# EVGP_Estop_Daugherboard.net
KiCad netlist of a schematic drawn in EAGLE
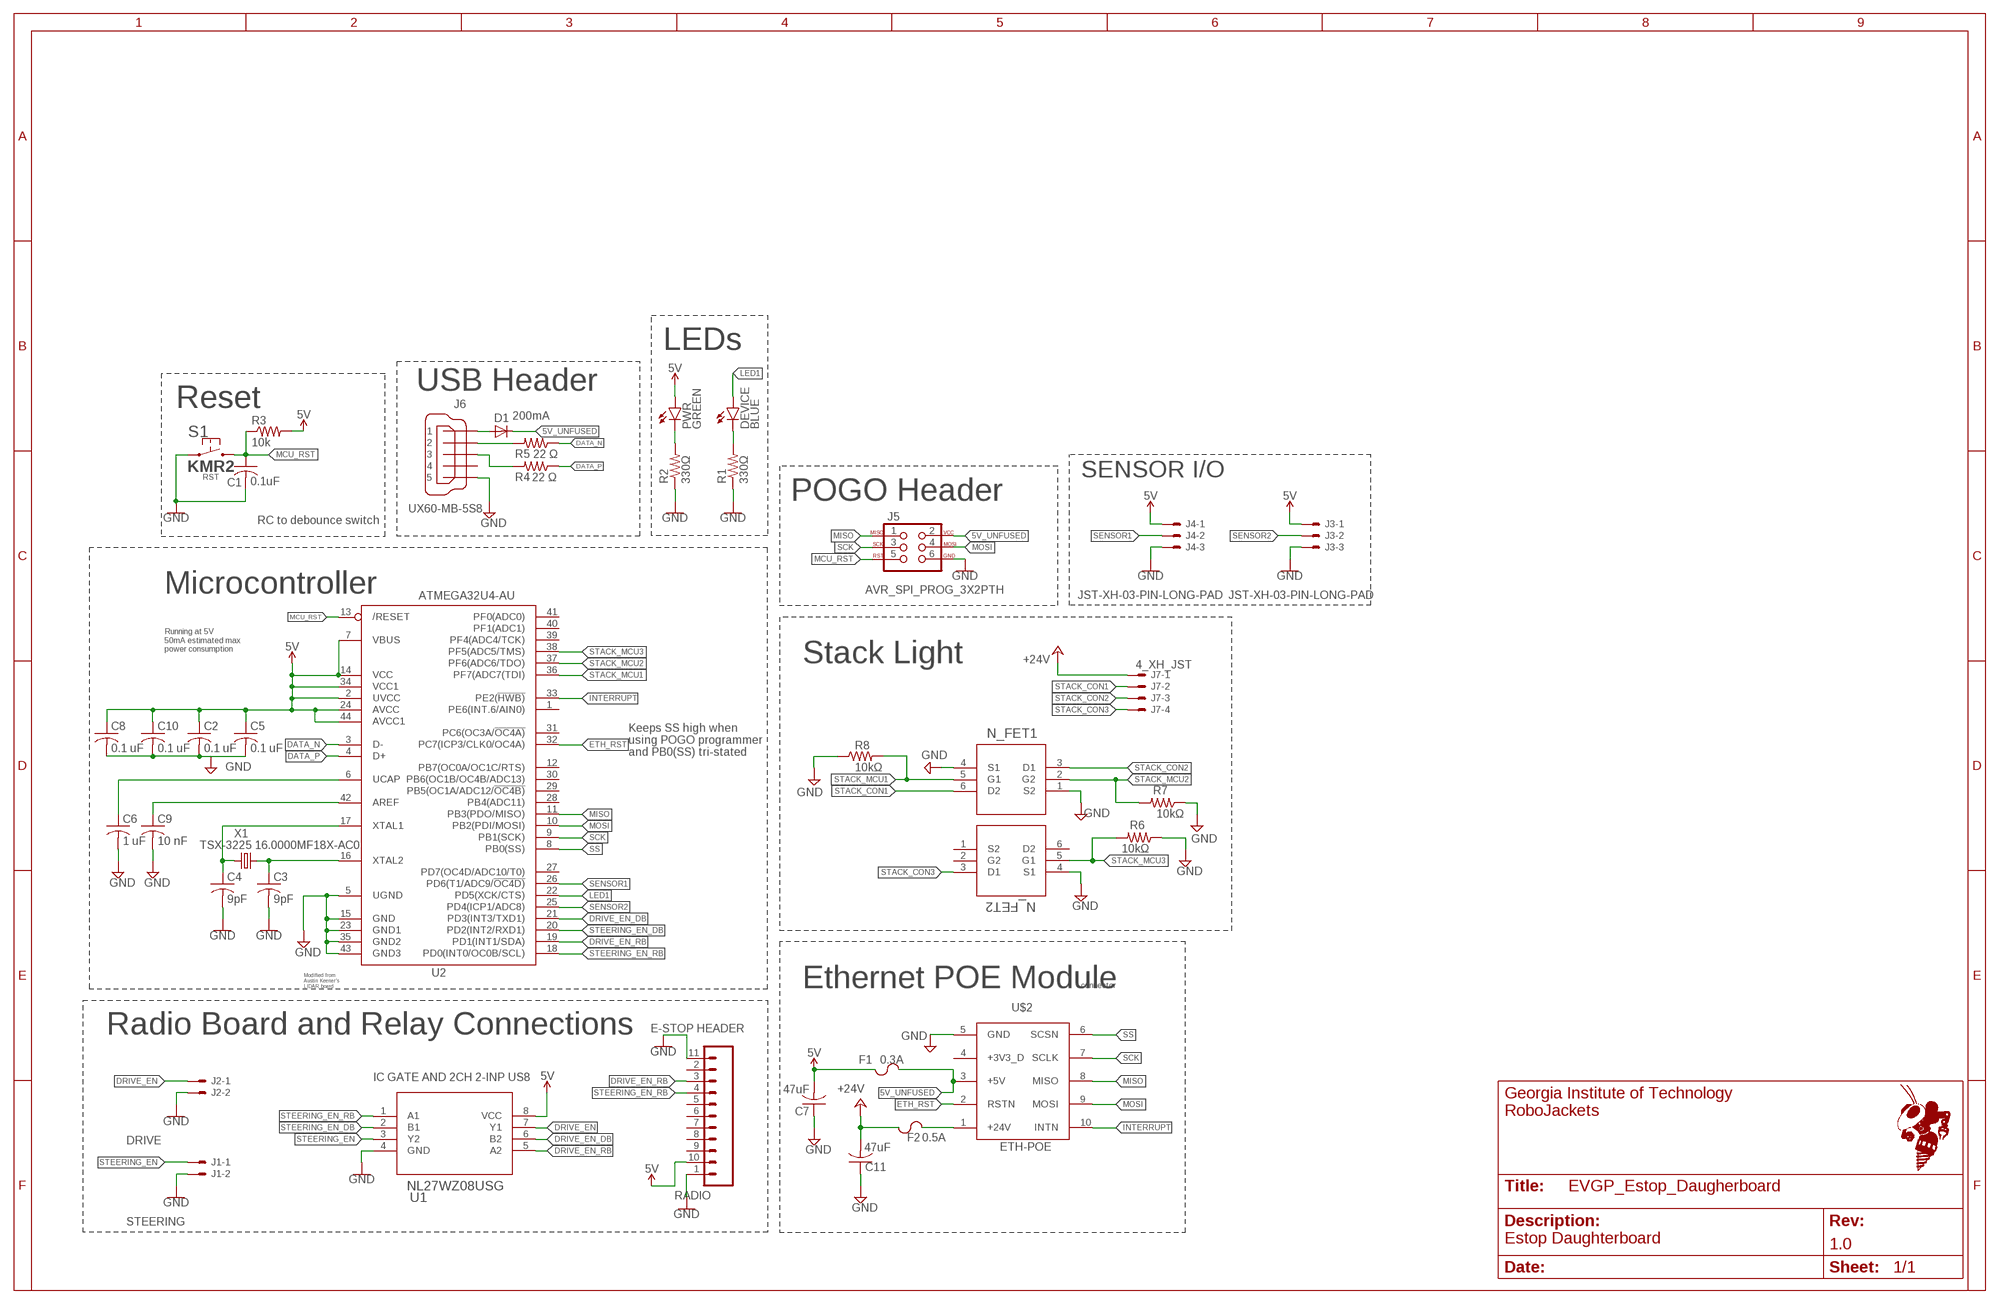
[diagram p0: schematic, sheet 1]

(export (version "E")
  (design (tool "Eeschema 10.0.6"))
  (components
    (comp (ref "C1")
      (value "0.1uF")
      (footprint "eagle-import:C0603")
      (libsource (lib "eagle-import") (part "C-USC0603"))
    )
    (comp (ref "C2")
      (value "0.1 uF")
      (footprint "eagle-import:C0603")
      (libsource (lib "eagle-import") (part "resistor_348_C-USC0603"))
    )
    (comp (ref "C3")
      (value "9pF")
      (footprint "eagle-import:C0603")
      (libsource (lib "eagle-import") (part "resistor_348_C-USC0603"))
    )
    (comp (ref "C4")
      (value "9pF")
      (footprint "eagle-import:C0603")
      (libsource (lib "eagle-import") (part "resistor_348_C-USC0603"))
    )
    (comp (ref "C5")
      (value "0.1 uF")
      (footprint "eagle-import:C0603")
      (libsource (lib "eagle-import") (part "resistor_348_C-USC0603"))
    )
    (comp (ref "C6")
      (value "1 uF")
      (footprint "eagle-import:C0603")
      (libsource (lib "eagle-import") (part "resistor_348_C-USC0603"))
    )
    (comp (ref "C7")
      (value "47uF")
      (footprint "eagle-import:C1206")
      (libsource (lib "eagle-import") (part "C-USC1206"))
    )
    (comp (ref "C8")
      (value "0.1 uF")
      (footprint "eagle-import:C0603")
      (libsource (lib "eagle-import") (part "resistor_348_C-USC0603"))
    )
    (comp (ref "C9")
      (value "10 nF")
      (footprint "eagle-import:C0603")
      (libsource (lib "eagle-import") (part "resistor_348_C-USC0603"))
    )
    (comp (ref "C10")
      (value "0.1 uF")
      (footprint "eagle-import:C0603")
      (libsource (lib "eagle-import") (part "resistor_348_C-USC0603"))
    )
    (comp (ref "C11")
      (value "47uF")
      (footprint "eagle-import:C1206")
      (libsource (lib "eagle-import") (part "C-USC1206"))
    )
    (comp (ref "D1")
      (value "200mA")
      (footprint "eagle-import:SOD323-R")
      (libsource (lib "eagle-import") (part "DIODE-SOD323-R"))
    )
    (comp (ref "DEVICE")
      (value "BLUE")
      (footprint "eagle-import:CHIP-LED0603")
      (libsource (lib "eagle-import") (part "LEDCHIP-LED0603"))
    )
    (comp (ref "F1")
      (value "0.3A")
      (footprint "eagle-import:F1206")
      (libsource (lib "eagle-import") (part "CHIP_FUSE1206"))
    )
    (comp (ref "F2")
      (value "0.5A")
      (footprint "eagle-import:F1206")
      (libsource (lib "eagle-import") (part "CHIP_FUSE1206"))
    )
    (comp (ref "J1")
      (value "STEERING")
      (footprint "eagle-import:JST-XH-02-PACKAGE-LONG-PAD")
      (libsource (lib "eagle-import") (part "JST-XH-02-PIN-LONG-PAD"))
    )
    (comp (ref "J2")
      (value "DRIVE")
      (footprint "eagle-import:JST-XH-02-PACKAGE-LONG-PAD")
      (libsource (lib "eagle-import") (part "JST-XH-02-PIN-LONG-PAD"))
    )
    (comp (ref "J3")
      (value "JST-XH-03-PIN-LONG-PAD")
      (footprint "eagle-import:JST-XH-03-PACKAGE-LONG-PAD")
      (libsource (lib "eagle-import") (part "JST-XH-03-PIN-LONG-PAD"))
    )
    (comp (ref "J4")
      (value "JST-XH-03-PIN-LONG-PAD")
      (footprint "eagle-import:JST-XH-03-PACKAGE-LONG-PAD")
      (libsource (lib "eagle-import") (part "JST-XH-03-PIN-LONG-PAD"))
    )
    (comp (ref "J5")
      (value "AVR_SPI_PROG_3X2PTH")
      (footprint "eagle-import:2X3")
      (libsource (lib "eagle-import") (part "AVR_SPI_PROG_3X2PTH"))
    )
    (comp (ref "J6")
      (value "UX60-MB-5S8")
      (footprint "eagle-import:UX60-MB-5S8")
      (libsource (lib "eagle-import") (part "UX60-MB-5S?8"))
    )
    (comp (ref "J7")
      (value "4_XH_JST")
      (footprint "eagle-import:JST-XH-04-PACKAGE-LONG-PAD")
      (libsource (lib "eagle-import") (part "JST-XH-04-PIN-LONG-PAD"))
    )
    (comp (ref "PWR")
      (value "GREEN")
      (footprint "eagle-import:CHIP-LED0603")
      (libsource (lib "eagle-import") (part "LEDCHIP-LED0603"))
    )
    (comp (ref "Q1")
      (value "N_FET2")
      (footprint "eagle-import:SOT-363")
      (fields (field (name "MANUFACTURER_PART_NUMBER") "BSS84DW7F"))
      (libsource (lib "eagle-import") (part "BSS84DW-7-F"))
    )
    (comp (ref "Q2")
      (value "N_FET1")
      (footprint "eagle-import:SOT-363")
      (fields (field (name "MANUFACTURER_PART_NUMBER") "BSS84DW7F"))
      (libsource (lib "eagle-import") (part "BSS84DW-7-F"))
    )
    (comp (ref "R1")
      (value "330Ω")
      (footprint "eagle-import:R0603")
      (libsource (lib "eagle-import") (part "R-US_R0603"))
    )
    (comp (ref "R2")
      (value "330Ω")
      (footprint "eagle-import:R0603")
      (libsource (lib "eagle-import") (part "R-US_R0603"))
    )
    (comp (ref "R3")
      (value "10k")
      (footprint "eagle-import:R0603")
      (libsource (lib "eagle-import") (part "R-US_R0603"))
    )
    (comp (ref "R4")
      (value "22 Ω")
      (footprint "eagle-import:R0603")
      (libsource (lib "eagle-import") (part "R-US_R0603"))
    )
    (comp (ref "R5")
      (value "22 Ω")
      (footprint "eagle-import:R0603")
      (libsource (lib "eagle-import") (part "R-US_R0603"))
    )
    (comp (ref "R6")
      (value "10kΩ")
      (footprint "eagle-import:R0603")
      (libsource (lib "eagle-import") (part "R-US_R0603"))
    )
    (comp (ref "R7")
      (value "10kΩ")
      (footprint "eagle-import:R0603")
      (libsource (lib "eagle-import") (part "R-US_R0603"))
    )
    (comp (ref "R8")
      (value "10kΩ")
      (footprint "eagle-import:R0603")
      (libsource (lib "eagle-import") (part "R-US_R0603"))
    )
    (comp (ref "RADIO")
      (value "E-STOP HEADER")
      (footprint "eagle-import:RADIO_V1.3")
      (libsource (lib "eagle-import") (part "ESTOP_RADIO"))
    )
    (comp (ref "S1")
      (value "KMR2")
      (footprint "eagle-import:KMR2")
      (fields (field (name "FUNCTION") "Reset") (field (name "FUNCTION_1") "RST"))
      (libsource (lib "eagle-import") (part "KMR2"))
    )
    (comp (ref "U$2")
      (value "ETH-POE")
      (footprint "eagle-import:HDRVR10W64P4000X254_2X5_1016X508X254B")
      (libsource (lib "eagle-import") (part "ETH-POE"))
    )
    (comp (ref "U1")
      (value "NL27WZ08USG")
      (footprint "eagle-import:US8_2P40X2P10")
      (libsource (lib "eagle-import") (part "NL27WZ08USG"))
    )
    (comp (ref "U2")
      (value "ATMEGA32U4-AU")
      (footprint "eagle-import:TQFP44")
      (libsource (lib "eagle-import") (part "ATMEGA32U4-AU"))
    )
    (comp (ref "X1")
      (value "TSX-3225 16.0000MF18X-AC0")
      (footprint "eagle-import:XTAL-3.2X2.5")
      (libsource (lib "eagle-import") (part "XTAL-3.2X2.5"))
    )
  )
  (nets
    (net (code "1") (name "+24V") (class "Default")
      (node (ref "C11") (pin "2") (pinfunction "2_2") (pintype "passive"))
      (node (ref "F2") (pin "1") (pinfunction "1_1") (pintype "bidirectional"))
      (node (ref "J7") (pin "1") (pinfunction "S_1") (pintype "passive"))
    )
    (net (code "2") (name "5V") (class "Default")
      (node (ref "C10") (pin "1") (pinfunction "1_1") (pintype "passive"))
      (node (ref "C2") (pin "1") (pinfunction "1_1") (pintype "passive"))
      (node (ref "C5") (pin "1") (pinfunction "1_1") (pintype "passive"))
      (node (ref "C7") (pin "2") (pinfunction "2_2") (pintype "passive"))
      (node (ref "C8") (pin "1") (pinfunction "1_1") (pintype "passive"))
      (node (ref "F1") (pin "1") (pinfunction "1_1") (pintype "bidirectional"))
      (node (ref "J3") (pin "1") (pinfunction "S_1") (pintype "passive"))
      (node (ref "J4") (pin "1") (pinfunction "S_1") (pintype "passive"))
      (node (ref "PWR") (pin "A") (pinfunction "A_A") (pintype "passive"))
      (node (ref "R3") (pin "2") (pinfunction "2_2") (pintype "passive"))
      (node (ref "RADIO") (pin "10") (pinfunction "5V_10") (pintype "passive"))
      (node (ref "U1") (pin "8") (pinfunction "VCC_8") (pintype "power_in"))
      (node (ref "U2") (pin "14") (pinfunction "VCC_14") (pintype "bidirectional"))
      (node (ref "U2") (pin "2") (pinfunction "UVCC_2") (pintype "bidirectional"))
      (node (ref "U2") (pin "24") (pinfunction "AVCC_24") (pintype "bidirectional"))
      (node (ref "U2") (pin "34") (pinfunction "VCC1_34") (pintype "bidirectional"))
      (node (ref "U2") (pin "44") (pinfunction "AVCC1_44") (pintype "bidirectional"))
      (node (ref "U2") (pin "7") (pinfunction "VBUS_7") (pintype "bidirectional"))
    )
    (net (code "3") (name "5V_UNFUSED") (class "Default")
      (node (ref "D1") (pin "C") (pinfunction "C_C") (pintype "passive"))
      (node (ref "F1") (pin "2") (pinfunction "2_2") (pintype "bidirectional"))
      (node (ref "J5") (pin "2") (pinfunction "2_2") (pintype "passive"))
      (node (ref "U$2") (pin "3") (pinfunction "+5V_3") (pintype "bidirectional"))
    )
    (net (code "4") (name "DATA_N") (class "Default")
      (node (ref "R5") (pin "1") (pinfunction "1_1") (pintype "passive"))
      (node (ref "U2") (pin "3") (pinfunction "D-_3") (pintype "bidirectional"))
    )
    (net (code "5") (name "DATA_P") (class "Default")
      (node (ref "R4") (pin "1") (pinfunction "1_1") (pintype "passive"))
      (node (ref "U2") (pin "4") (pinfunction "D+_4") (pintype "bidirectional"))
    )
    (net (code "6") (name "DRIVE_EN") (class "Default")
      (node (ref "J2") (pin "1") (pinfunction "S_1") (pintype "passive"))
      (node (ref "U1") (pin "7") (pinfunction "Y1_7") (pintype "output"))
    )
    (net (code "7") (name "DRIVE_EN_DB") (class "Default")
      (node (ref "U1") (pin "6") (pinfunction "B2_6") (pintype "input"))
      (node (ref "U2") (pin "21") (pinfunction "PD3(INT3/TXD1)_21") (pintype "bidirectional"))
    )
    (net (code "8") (name "DRIVE_EN_RB") (class "Default")
      (node (ref "RADIO") (pin "3") (pinfunction "D1_3") (pintype "passive"))
      (node (ref "U1") (pin "5") (pinfunction "A2_5") (pintype "input"))
      (node (ref "U2") (pin "19") (pinfunction "PD1(INT1/SDA)_19") (pintype "bidirectional"))
    )
    (net (code "9") (name "ETH_RST") (class "Default")
      (node (ref "U$2") (pin "2") (pinfunction "RSTN_2") (pintype "bidirectional"))
      (node (ref "U2") (pin "32") (pinfunction "PC7(ICP3/CLK0/OC4A)_32") (pintype "bidirectional"))
    )
    (net (code "10") (name "GND") (class "Default")
      (node (ref "C1") (pin "2") (pinfunction "2_2") (pintype "passive"))
      (node (ref "C10") (pin "2") (pinfunction "2_2") (pintype "passive"))
      (node (ref "C11") (pin "1") (pinfunction "1_1") (pintype "passive"))
      (node (ref "C2") (pin "2") (pinfunction "2_2") (pintype "passive"))
      (node (ref "C3") (pin "2") (pinfunction "2_2") (pintype "passive"))
      (node (ref "C4") (pin "2") (pinfunction "2_2") (pintype "passive"))
      (node (ref "C5") (pin "2") (pinfunction "2_2") (pintype "passive"))
      (node (ref "C6") (pin "2") (pinfunction "2_2") (pintype "passive"))
      (node (ref "C7") (pin "1") (pinfunction "1_1") (pintype "passive"))
      (node (ref "C8") (pin "2") (pinfunction "2_2") (pintype "passive"))
      (node (ref "C9") (pin "2") (pinfunction "2_2") (pintype "passive"))
      (node (ref "J1") (pin "2") (pinfunction "S_2") (pintype "passive"))
      (node (ref "J2") (pin "2") (pinfunction "S_2") (pintype "passive"))
      (node (ref "J3") (pin "3") (pinfunction "S_3") (pintype "passive"))
      (node (ref "J4") (pin "3") (pinfunction "S_3") (pintype "passive"))
      (node (ref "J5") (pin "6") (pinfunction "6_6") (pintype "passive"))
      (node (ref "J6") (pin "5") (pinfunction "5_5") (pintype "passive"))
      (node (ref "Q1") (pin "4") (pinfunction "S1_4") (pintype "passive"))
      (node (ref "Q2") (pin "1") (pinfunction "S2_1") (pintype "passive"))
      (node (ref "Q2") (pin "4") (pinfunction "S1_4") (pintype "passive"))
      (node (ref "R1") (pin "1") (pinfunction "1_1") (pintype "passive"))
      (node (ref "R2") (pin "1") (pinfunction "1_1") (pintype "passive"))
      (node (ref "R6") (pin "1") (pinfunction "1_1") (pintype "passive"))
      (node (ref "R7") (pin "1") (pinfunction "1_1") (pintype "passive"))
      (node (ref "R8") (pin "1") (pinfunction "1_1") (pintype "passive"))
      (node (ref "RADIO") (pin "1") (pinfunction "GND_1") (pintype "passive"))
      (node (ref "RADIO") (pin "11") (pinfunction "GND_11") (pintype "passive"))
      (node (ref "S1") (pin "1.1") (pinfunction "1_1.1") (pintype "passive"))
      (node (ref "S1") (pin "1.2") (pinfunction "1_1.2") (pintype "passive"))
      (node (ref "U$2") (pin "5") (pinfunction "GND_5") (pintype "bidirectional"))
      (node (ref "U1") (pin "4") (pinfunction "GND_4") (pintype "power_in"))
      (node (ref "U2") (pin "15") (pinfunction "GND_15") (pintype "bidirectional"))
      (node (ref "U2") (pin "23") (pinfunction "GND1_23") (pintype "bidirectional"))
      (node (ref "U2") (pin "35") (pinfunction "GND2_35") (pintype "bidirectional"))
      (node (ref "U2") (pin "43") (pinfunction "GND3_43") (pintype "bidirectional"))
      (node (ref "U2") (pin "5") (pinfunction "UGND_5") (pintype "bidirectional"))
    )
    (net (code "11") (name "INTERRUPT") (class "Default")
      (node (ref "U$2") (pin "10") (pinfunction "INTN_10") (pintype "bidirectional"))
      (node (ref "U2") (pin "33") (pinfunction "PE2(~{HWB})_33") (pintype "bidirectional"))
    )
    (net (code "12") (name "LED1") (class "Default")
      (node (ref "DEVICE") (pin "A") (pinfunction "A_A") (pintype "passive"))
      (node (ref "U2") (pin "22") (pinfunction "PD5(XCK/CTS)_22") (pintype "bidirectional"))
    )
    (net (code "13") (name "MCU_RST") (class "Default")
      (node (ref "C1") (pin "1") (pinfunction "1_1") (pintype "passive"))
      (node (ref "J5") (pin "5") (pinfunction "5_5") (pintype "passive"))
      (node (ref "R3") (pin "1") (pinfunction "1_1") (pintype "passive"))
      (node (ref "S1") (pin "2.1") (pinfunction "2_2.1") (pintype "passive"))
      (node (ref "S1") (pin "2.2") (pinfunction "2_2.2") (pintype "passive"))
      (node (ref "U2") (pin "13") (pinfunction "/RESET_13") (pintype "bidirectional"))
    )
    (net (code "14") (name "MISO") (class "Default")
      (node (ref "J5") (pin "1") (pinfunction "1_1") (pintype "passive"))
      (node (ref "U$2") (pin "8") (pinfunction "MISO_8") (pintype "bidirectional"))
      (node (ref "U2") (pin "11") (pinfunction "PB3(PDO/MISO)_11") (pintype "bidirectional"))
    )
    (net (code "15") (name "MOSI") (class "Default")
      (node (ref "J5") (pin "4") (pinfunction "4_4") (pintype "passive"))
      (node (ref "U$2") (pin "9") (pinfunction "MOSI_9") (pintype "bidirectional"))
      (node (ref "U2") (pin "10") (pinfunction "PB2(PDI/MOSI)_10") (pintype "bidirectional"))
    )
    (net (code "16") (name "Net-(D1-PadA)") (class "Default")
      (node (ref "D1") (pin "A") (pinfunction "A_A") (pintype "passive"))
      (node (ref "J6") (pin "1") (pinfunction "1_1") (pintype "passive"))
    )
    (net (code "17") (name "Net-(DEVICE-PadC)") (class "Default")
      (node (ref "DEVICE") (pin "C") (pinfunction "C_C") (pintype "passive"))
      (node (ref "R1") (pin "2") (pinfunction "2_2") (pintype "passive"))
    )
    (net (code "18") (name "Net-(J6-Pad2)") (class "Default")
      (node (ref "J6") (pin "2") (pinfunction "2_2") (pintype "passive"))
      (node (ref "R5") (pin "2") (pinfunction "2_2") (pintype "passive"))
    )
    (net (code "19") (name "Net-(J6-Pad3)") (class "Default")
      (node (ref "J6") (pin "3") (pinfunction "3_3") (pintype "passive"))
      (node (ref "R4") (pin "2") (pinfunction "2_2") (pintype "passive"))
    )
    (net (code "20") (name "Net-(PWR-PadC)") (class "Default")
      (node (ref "PWR") (pin "C") (pinfunction "C_C") (pintype "passive"))
      (node (ref "R2") (pin "2") (pinfunction "2_2") (pintype "passive"))
    )
    (net (code "21") (name "Net-(U$2-+24V)") (class "Default")
      (node (ref "F2") (pin "2") (pinfunction "2_2") (pintype "bidirectional"))
      (node (ref "U$2") (pin "1") (pinfunction "+24V_1") (pintype "bidirectional"))
    )
    (net (code "22") (name "Net-(U2-AREF)") (class "Default")
      (node (ref "C9") (pin "1") (pinfunction "1_1") (pintype "passive"))
      (node (ref "U2") (pin "42") (pinfunction "AREF_42") (pintype "bidirectional"))
    )
    (net (code "23") (name "Net-(U2-UCAP)") (class "Default")
      (node (ref "C6") (pin "1") (pinfunction "1_1") (pintype "passive"))
      (node (ref "U2") (pin "6") (pinfunction "UCAP_6") (pintype "bidirectional"))
    )
    (net (code "24") (name "Net-(U2-XTAL1)") (class "Default")
      (node (ref "C4") (pin "1") (pinfunction "1_1") (pintype "passive"))
      (node (ref "U2") (pin "17") (pinfunction "XTAL1_17") (pintype "bidirectional"))
      (node (ref "X1") (pin "1") (pinfunction "1_1") (pintype "passive"))
    )
    (net (code "25") (name "Net-(U2-XTAL2)") (class "Default")
      (node (ref "C3") (pin "1") (pinfunction "1_1") (pintype "passive"))
      (node (ref "U2") (pin "16") (pinfunction "XTAL2_16") (pintype "bidirectional"))
      (node (ref "X1") (pin "3") (pinfunction "2_3") (pintype "passive"))
    )
    (net (code "26") (name "SCK") (class "Default")
      (node (ref "J5") (pin "3") (pinfunction "3_3") (pintype "passive"))
      (node (ref "U$2") (pin "7") (pinfunction "SCLK_7") (pintype "bidirectional"))
      (node (ref "U2") (pin "9") (pinfunction "PB1(SCK)_9") (pintype "bidirectional"))
    )
    (net (code "27") (name "SENSOR1") (class "Default")
      (node (ref "J4") (pin "2") (pinfunction "S_2") (pintype "passive"))
      (node (ref "U2") (pin "26") (pinfunction "PD6(T1/ADC9/~{OC4D})_26") (pintype "bidirectional"))
    )
    (net (code "28") (name "SENSOR2") (class "Default")
      (node (ref "J3") (pin "2") (pinfunction "S_2") (pintype "passive"))
      (node (ref "U2") (pin "25") (pinfunction "PD4(ICP1/ADC8)_25") (pintype "bidirectional"))
    )
    (net (code "29") (name "SS") (class "Default")
      (node (ref "U$2") (pin "6") (pinfunction "SCSN_6") (pintype "bidirectional"))
      (node (ref "U2") (pin "8") (pinfunction "PB0(SS)_8") (pintype "bidirectional"))
    )
    (net (code "30") (name "STACK_CON1") (class "Default")
      (node (ref "J7") (pin "2") (pinfunction "S_2") (pintype "passive"))
      (node (ref "Q2") (pin "6") (pinfunction "D2_6") (pintype "passive"))
    )
    (net (code "31") (name "STACK_CON2") (class "Default")
      (node (ref "J7") (pin "3") (pinfunction "S_3") (pintype "passive"))
      (node (ref "Q2") (pin "3") (pinfunction "D1_3") (pintype "passive"))
    )
    (net (code "32") (name "STACK_CON3") (class "Default")
      (node (ref "J7") (pin "4") (pinfunction "S_4") (pintype "passive"))
      (node (ref "Q1") (pin "3") (pinfunction "D1_3") (pintype "passive"))
    )
    (net (code "33") (name "STACK_MCU1") (class "Default")
      (node (ref "Q2") (pin "5") (pinfunction "G1_5") (pintype "passive"))
      (node (ref "R8") (pin "2") (pinfunction "2_2") (pintype "passive"))
      (node (ref "U2") (pin "36") (pinfunction "PF7(ADC7(TDI)_36") (pintype "bidirectional"))
    )
    (net (code "34") (name "STACK_MCU2") (class "Default")
      (node (ref "Q2") (pin "2") (pinfunction "G2_2") (pintype "passive"))
      (node (ref "R7") (pin "2") (pinfunction "2_2") (pintype "passive"))
      (node (ref "U2") (pin "37") (pinfunction "PF6(ADC6/TDO)_37") (pintype "bidirectional"))
    )
    (net (code "35") (name "STACK_MCU3") (class "Default")
      (node (ref "Q1") (pin "5") (pinfunction "G1_5") (pintype "passive"))
      (node (ref "R6") (pin "2") (pinfunction "2_2") (pintype "passive"))
      (node (ref "U2") (pin "38") (pinfunction "PF5(ADC5/TMS)_38") (pintype "bidirectional"))
    )
    (net (code "36") (name "STEERING_EN") (class "Default")
      (node (ref "J1") (pin "1") (pinfunction "S_1") (pintype "passive"))
      (node (ref "U1") (pin "3") (pinfunction "Y2_3") (pintype "output"))
    )
    (net (code "37") (name "STEERING_EN_DB") (class "Default")
      (node (ref "U1") (pin "2") (pinfunction "B1_2") (pintype "input"))
      (node (ref "U2") (pin "20") (pinfunction "PD2(INT2/RXD1)_20") (pintype "bidirectional"))
    )
    (net (code "38") (name "STEERING_EN_RB") (class "Default")
      (node (ref "RADIO") (pin "4") (pinfunction "D2_4") (pintype "passive"))
      (node (ref "U1") (pin "1") (pinfunction "A1_1") (pintype "input"))
      (node (ref "U2") (pin "18") (pinfunction "PD0(INT0/OC0B/SCL)_18") (pintype "bidirectional"))
    )
    (net (code "39") (name "unconnected-(J6-Pad4)") (class "Default")
      (node (ref "J6") (pin "4") (pinfunction "4_4") (pintype "passive"))
    )
    (net (code "40") (name "unconnected-(Q1-D2-Pad6)") (class "Default")
      (node (ref "Q1") (pin "6") (pinfunction "D2_6") (pintype "passive"))
    )
    (net (code "41") (name "unconnected-(Q1-G2-Pad2)") (class "Default")
      (node (ref "Q1") (pin "2") (pinfunction "G2_2") (pintype "passive"))
    )
    (net (code "42") (name "unconnected-(Q1-S2-Pad1)") (class "Default")
      (node (ref "Q1") (pin "1") (pinfunction "S2_1") (pintype "passive"))
    )
    (net (code "43") (name "unconnected-(RADIO-D3-Pad5)") (class "Default")
      (node (ref "RADIO") (pin "5") (pinfunction "D3_5") (pintype "passive"))
    )
    (net (code "44") (name "unconnected-(RADIO-D4-Pad6)") (class "Default")
      (node (ref "RADIO") (pin "6") (pinfunction "D4_6") (pintype "passive"))
    )
    (net (code "45") (name "unconnected-(RADIO-D5-Pad7)") (class "Default")
      (node (ref "RADIO") (pin "7") (pinfunction "D5_7") (pintype "passive"))
    )
    (net (code "46") (name "unconnected-(RADIO-D6-Pad8)") (class "Default")
      (node (ref "RADIO") (pin "8") (pinfunction "D6_8") (pintype "passive"))
    )
    (net (code "47") (name "unconnected-(RADIO-D7-Pad9)") (class "Default")
      (node (ref "RADIO") (pin "9") (pinfunction "D7_9") (pintype "passive"))
    )
    (net (code "48") (name "unconnected-(RADIO-RST-Pad2)") (class "Default")
      (node (ref "RADIO") (pin "2") (pinfunction "RST_2") (pintype "passive"))
    )
    (net (code "49") (name "unconnected-(U$2-+3V3_D-Pad4)") (class "Default")
      (node (ref "U$2") (pin "4") (pinfunction "+3V3_D_4") (pintype "bidirectional"))
    )
    (net (code "50") (name "unconnected-(U2-PB4(ADC11)-Pad28)") (class "Default")
      (node (ref "U2") (pin "28") (pinfunction "PB4(ADC11)_28") (pintype "bidirectional"))
    )
    (net (code "51") (name "unconnected-(U2-PB5(OC1A{slash}ADC12{slash}~{OC4B})-Pad29)") (class "Default")
      (node (ref "U2") (pin "29") (pinfunction "PB5(OC1A/ADC12/~{OC4B})_29") (pintype "bidirectional"))
    )
    (net (code "52") (name "unconnected-(U2-PB6(OC1B{slash}OC4B{slash}ADC13)-Pad30)") (class "Default")
      (node (ref "U2") (pin "30") (pinfunction "PB6(OC1B/OC4B/ADC13)_30") (pintype "bidirectional"))
    )
    (net (code "53") (name "unconnected-(U2-PB7(OC0A{slash}OC1C{slash}RTS)-Pad12)") (class "Default")
      (node (ref "U2") (pin "12") (pinfunction "PB7(OC0A/OC1C/RTS)_12") (pintype "bidirectional"))
    )
    (net (code "54") (name "unconnected-(U2-PC6(OC3A{slash}~{OC4A})-Pad31)") (class "Default")
      (node (ref "U2") (pin "31") (pinfunction "PC6(OC3A/~{OC4A})_31") (pintype "bidirectional"))
    )
    (net (code "55") (name "unconnected-(U2-PD7(OC4D{slash}ADC10{slash}T0)-Pad27)") (class "Default")
      (node (ref "U2") (pin "27") (pinfunction "PD7(OC4D/ADC10/T0)_27") (pintype "bidirectional"))
    )
    (net (code "56") (name "unconnected-(U2-PE6(INT.6{slash}AIN0)-Pad1)") (class "Default")
      (node (ref "U2") (pin "1") (pinfunction "PE6(INT.6/AIN0)_1") (pintype "bidirectional"))
    )
    (net (code "57") (name "unconnected-(U2-PF0(ADC0)-Pad41)") (class "Default")
      (node (ref "U2") (pin "41") (pinfunction "PF0(ADC0)_41") (pintype "bidirectional"))
    )
    (net (code "58") (name "unconnected-(U2-PF1(ADC1)-Pad40)") (class "Default")
      (node (ref "U2") (pin "40") (pinfunction "PF1(ADC1)_40") (pintype "bidirectional"))
    )
    (net (code "59") (name "unconnected-(U2-PF4(ADC4{slash}TCK)-Pad39)") (class "Default")
      (node (ref "U2") (pin "39") (pinfunction "PF4(ADC4/TCK)_39") (pintype "bidirectional"))
    )
  )
)
